# hr.net
KiCad netlist of a schematic drawn in EAGLE
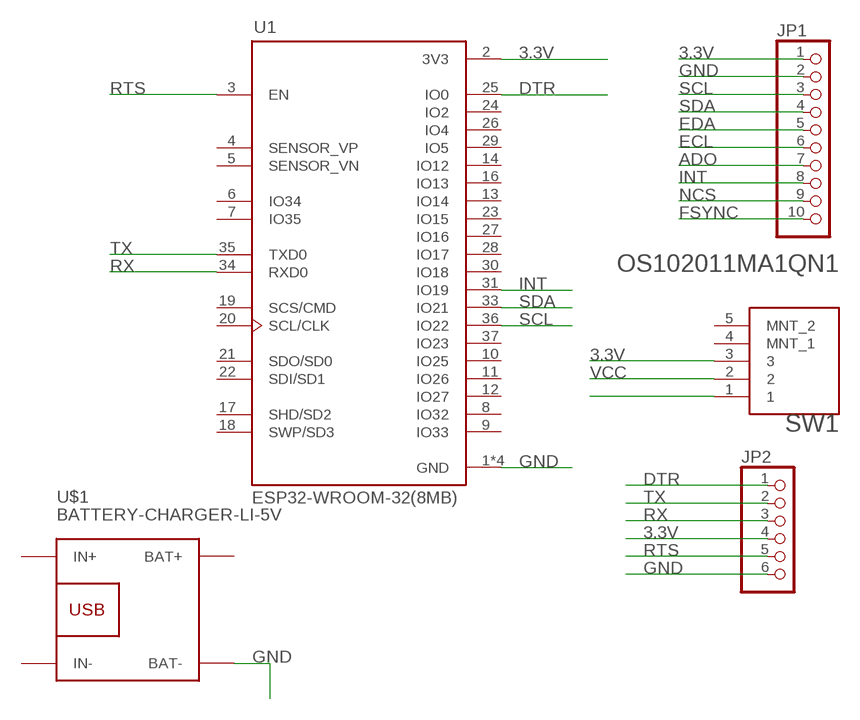
[diagram p0: schematic, sheet 1]

(export (version "E")
  (design (tool "Eeschema 10.0.6"))
  (components
    (comp (ref "JP1")
      (value "PINHD-1X10")
      (footprint "eagle-import:1X10")
      (libsource (lib "eagle-import") (part "PINHD-1X10"))
    )
    (comp (ref "JP2")
      (value "PINHD-1X6")
      (footprint "eagle-import:1X06")
      (libsource (lib "eagle-import") (part "PINHD-1X6"))
    )
    (comp (ref "SW1")
      (value "C&K_OS102011MA1QN1C&K_OS102011MA1QN1_0_0")
      (footprint "eagle-import:C&K_OS102011MA1QN1_0")
      (fields
        (field (name "DIGIKEY_PART_NUMBER") "CKN9559-ND")
        (field (name "MF") "C&K")
        (field (name "MOUSER_PART_NUMBER") "OS102011MA1QN1")
      )
      (libsource (lib "eagle-import") (part "C&K_OS102011MA1QN1C&K_OS102011MA1QN1_0_0"))
    )
    (comp (ref "U$1")
      (value "BATTERY-CHARGER-LI-5V")
      (footprint "eagle-import:BATTERY-CHARGER-LI-5V")
      (libsource (lib "eagle-import") (part "BATTERY-CHARGER-LI-5V"))
    )
    (comp (ref "U1")
      (value "ESP32-WROOM-32(8MB)")
      (footprint "eagle-import:MODULE_ESP32-WROOM-32(8MB)")
      (fields (field (name "MF") "Espressif Systems") (field (name "MP") "ESP32-WROOM-32 _8MB_"))
      (libsource (lib "eagle-import") (part "ESP32-WROOM-32(8MB)"))
    )
  )
  (nets
    (net (code "1") (name "/3.3V") (class "Default")
      (node (ref "JP1") (pin "1") (pinfunction "1_1") (pintype "passive"))
      (node (ref "JP2") (pin "4") (pinfunction "4_4") (pintype "passive"))
      (node (ref "SW1") (pin "3") (pinfunction "3_3") (pintype "passive"))
      (node (ref "U1") (pin "2") (pinfunction "3V3_2") (pintype "power_in"))
    )
    (net (code "2") (name "/ADO") (class "Default")
      (node (ref "JP1") (pin "7") (pinfunction "7_7") (pintype "passive"))
    )
    (net (code "3") (name "/DTR") (class "Default")
      (node (ref "JP2") (pin "1") (pinfunction "1_1") (pintype "passive"))
      (node (ref "U1") (pin "25") (pinfunction "IO0_25") (pintype "bidirectional"))
    )
    (net (code "4") (name "/ECL") (class "Default")
      (node (ref "JP1") (pin "6") (pinfunction "6_6") (pintype "passive"))
    )
    (net (code "5") (name "/EDA") (class "Default")
      (node (ref "JP1") (pin "5") (pinfunction "5_5") (pintype "passive"))
    )
    (net (code "6") (name "/FSYNC") (class "Default")
      (node (ref "JP1") (pin "10") (pinfunction "10_10") (pintype "passive"))
    )
    (net (code "7") (name "/GND") (class "Default")
      (node (ref "JP1") (pin "2") (pinfunction "2_2") (pintype "passive"))
      (node (ref "JP2") (pin "6") (pinfunction "6_6") (pintype "passive"))
      (node (ref "U$1") (pin "BAT-") (pinfunction "BAT-_BAT-") (pintype "bidirectional"))
      (node (ref "U1") (pin "1") (pinfunction "GND_1") (pintype "power_in"))
      (node (ref "U1") (pin "15") (pinfunction "GND_15") (pintype "power_in"))
      (node (ref "U1") (pin "38") (pinfunction "GND_38") (pintype "power_in"))
      (node (ref "U1") (pin "39") (pinfunction "GND_39") (pintype "power_in"))
    )
    (net (code "8") (name "/INT") (class "Default")
      (node (ref "JP1") (pin "8") (pinfunction "8_8") (pintype "passive"))
      (node (ref "U1") (pin "31") (pinfunction "IO19_31") (pintype "bidirectional"))
    )
    (net (code "9") (name "/NCS") (class "Default")
      (node (ref "JP1") (pin "9") (pinfunction "9_9") (pintype "passive"))
    )
    (net (code "10") (name "/RTS") (class "Default")
      (node (ref "JP2") (pin "5") (pinfunction "5_5") (pintype "passive"))
      (node (ref "U1") (pin "3") (pinfunction "EN_3") (pintype "input"))
    )
    (net (code "11") (name "/RX") (class "Default")
      (node (ref "JP2") (pin "3") (pinfunction "3_3") (pintype "passive"))
      (node (ref "U1") (pin "34") (pinfunction "RXD0_34") (pintype "bidirectional"))
    )
    (net (code "12") (name "/SCL") (class "Default")
      (node (ref "JP1") (pin "3") (pinfunction "3_3") (pintype "passive"))
      (node (ref "U1") (pin "36") (pinfunction "IO22_36") (pintype "bidirectional"))
    )
    (net (code "13") (name "/SDA") (class "Default")
      (node (ref "JP1") (pin "4") (pinfunction "4_4") (pintype "passive"))
      (node (ref "U1") (pin "33") (pinfunction "IO21_33") (pintype "bidirectional"))
    )
    (net (code "14") (name "/TX") (class "Default")
      (node (ref "JP2") (pin "2") (pinfunction "2_2") (pintype "passive"))
      (node (ref "U1") (pin "35") (pinfunction "TXD0_35") (pintype "bidirectional"))
    )
    (net (code "15") (name "/VCC") (class "Default")
      (node (ref "SW1") (pin "2") (pinfunction "2_2") (pintype "passive"))
    )
    (net (code "16") (name "unconnected-(SW1-MNT_1-Pad4)") (class "Default")
      (node (ref "SW1") (pin "4") (pinfunction "MNT_1_4") (pintype "passive"))
    )
    (net (code "17") (name "unconnected-(SW1-MNT_2-Pad5)") (class "Default")
      (node (ref "SW1") (pin "5") (pinfunction "MNT_2_5") (pintype "passive"))
    )
    (net (code "18") (name "unconnected-(SW1-Pad1)") (class "Default")
      (node (ref "SW1") (pin "1") (pinfunction "1_1") (pintype "passive"))
    )
    (net (code "19") (name "unconnected-(U$1-PadBAT+)") (class "Default")
      (node (ref "U$1") (pin "BAT+") (pinfunction "BAT+_BAT+") (pintype "bidirectional"))
    )
    (net (code "20") (name "unconnected-(U$1-PadIN+)") (class "Default")
      (node (ref "U$1") (pin "IN+") (pinfunction "IN+_IN+") (pintype "bidirectional"))
    )
    (net (code "21") (name "unconnected-(U$1-PadIN-)") (class "Default")
      (node (ref "U$1") (pin "IN-") (pinfunction "IN-_IN-") (pintype "bidirectional"))
    )
    (net (code "22") (name "unconnected-(U1-IO2-Pad24)") (class "Default")
      (node (ref "U1") (pin "24") (pinfunction "IO2_24") (pintype "bidirectional"))
    )
    (net (code "23") (name "unconnected-(U1-IO4-Pad26)") (class "Default")
      (node (ref "U1") (pin "26") (pinfunction "IO4_26") (pintype "bidirectional"))
    )
    (net (code "24") (name "unconnected-(U1-IO5-Pad29)") (class "Default")
      (node (ref "U1") (pin "29") (pinfunction "IO5_29") (pintype "bidirectional"))
    )
    (net (code "25") (name "unconnected-(U1-IO12-Pad14)") (class "Default")
      (node (ref "U1") (pin "14") (pinfunction "IO12_14") (pintype "bidirectional"))
    )
    (net (code "26") (name "unconnected-(U1-IO13-Pad16)") (class "Default")
      (node (ref "U1") (pin "16") (pinfunction "IO13_16") (pintype "bidirectional"))
    )
    (net (code "27") (name "unconnected-(U1-IO14-Pad13)") (class "Default")
      (node (ref "U1") (pin "13") (pinfunction "IO14_13") (pintype "bidirectional"))
    )
    (net (code "28") (name "unconnected-(U1-IO15-Pad23)") (class "Default")
      (node (ref "U1") (pin "23") (pinfunction "IO15_23") (pintype "bidirectional"))
    )
    (net (code "29") (name "unconnected-(U1-IO16-Pad27)") (class "Default")
      (node (ref "U1") (pin "27") (pinfunction "IO16_27") (pintype "bidirectional"))
    )
    (net (code "30") (name "unconnected-(U1-IO17-Pad28)") (class "Default")
      (node (ref "U1") (pin "28") (pinfunction "IO17_28") (pintype "bidirectional"))
    )
    (net (code "31") (name "unconnected-(U1-IO18-Pad30)") (class "Default")
      (node (ref "U1") (pin "30") (pinfunction "IO18_30") (pintype "bidirectional"))
    )
    (net (code "32") (name "unconnected-(U1-IO23-Pad37)") (class "Default")
      (node (ref "U1") (pin "37") (pinfunction "IO23_37") (pintype "bidirectional"))
    )
    (net (code "33") (name "unconnected-(U1-IO25-Pad10)") (class "Default")
      (node (ref "U1") (pin "10") (pinfunction "IO25_10") (pintype "bidirectional"))
    )
    (net (code "34") (name "unconnected-(U1-IO26-Pad11)") (class "Default")
      (node (ref "U1") (pin "11") (pinfunction "IO26_11") (pintype "bidirectional"))
    )
    (net (code "35") (name "unconnected-(U1-IO27-Pad12)") (class "Default")
      (node (ref "U1") (pin "12") (pinfunction "IO27_12") (pintype "bidirectional"))
    )
    (net (code "36") (name "unconnected-(U1-IO32-Pad8)") (class "Default")
      (node (ref "U1") (pin "8") (pinfunction "IO32_8") (pintype "bidirectional"))
    )
    (net (code "37") (name "unconnected-(U1-IO33-Pad9)") (class "Default")
      (node (ref "U1") (pin "9") (pinfunction "IO33_9") (pintype "bidirectional"))
    )
    (net (code "38") (name "unconnected-(U1-IO34-Pad6)") (class "Default")
      (node (ref "U1") (pin "6") (pinfunction "IO34_6") (pintype "input"))
    )
    (net (code "39") (name "unconnected-(U1-IO35-Pad7)") (class "Default")
      (node (ref "U1") (pin "7") (pinfunction "IO35_7") (pintype "input"))
    )
    (net (code "40") (name "unconnected-(U1-SCL{slash}CLK-Pad20)") (class "Default")
      (node (ref "U1") (pin "20") (pinfunction "SCL/CLK_20") (pintype "bidirectional"))
    )
    (net (code "41") (name "unconnected-(U1-SCS{slash}CMD-Pad19)") (class "Default")
      (node (ref "U1") (pin "19") (pinfunction "SCS/CMD_19") (pintype "bidirectional"))
    )
    (net (code "42") (name "unconnected-(U1-SDI{slash}SD1-Pad22)") (class "Default")
      (node (ref "U1") (pin "22") (pinfunction "SDI/SD1_22") (pintype "bidirectional"))
    )
    (net (code "43") (name "unconnected-(U1-SDO{slash}SD0-Pad21)") (class "Default")
      (node (ref "U1") (pin "21") (pinfunction "SDO/SD0_21") (pintype "bidirectional"))
    )
    (net (code "44") (name "unconnected-(U1-SENSOR_VN-Pad5)") (class "Default")
      (node (ref "U1") (pin "5") (pinfunction "SENSOR_VN_5") (pintype "input"))
    )
    (net (code "45") (name "unconnected-(U1-SENSOR_VP-Pad4)") (class "Default")
      (node (ref "U1") (pin "4") (pinfunction "SENSOR_VP_4") (pintype "input"))
    )
    (net (code "46") (name "unconnected-(U1-SHD{slash}SD2-Pad17)") (class "Default")
      (node (ref "U1") (pin "17") (pinfunction "SHD/SD2_17") (pintype "bidirectional"))
    )
    (net (code "47") (name "unconnected-(U1-SWP{slash}SD3-Pad18)") (class "Default")
      (node (ref "U1") (pin "18") (pinfunction "SWP/SD3_18") (pintype "bidirectional"))
    )
  )
)
